# SCH_Apple_II_Game_port_2024-02-08.net
KiCad netlist of a schematic drawn in EasyEDA
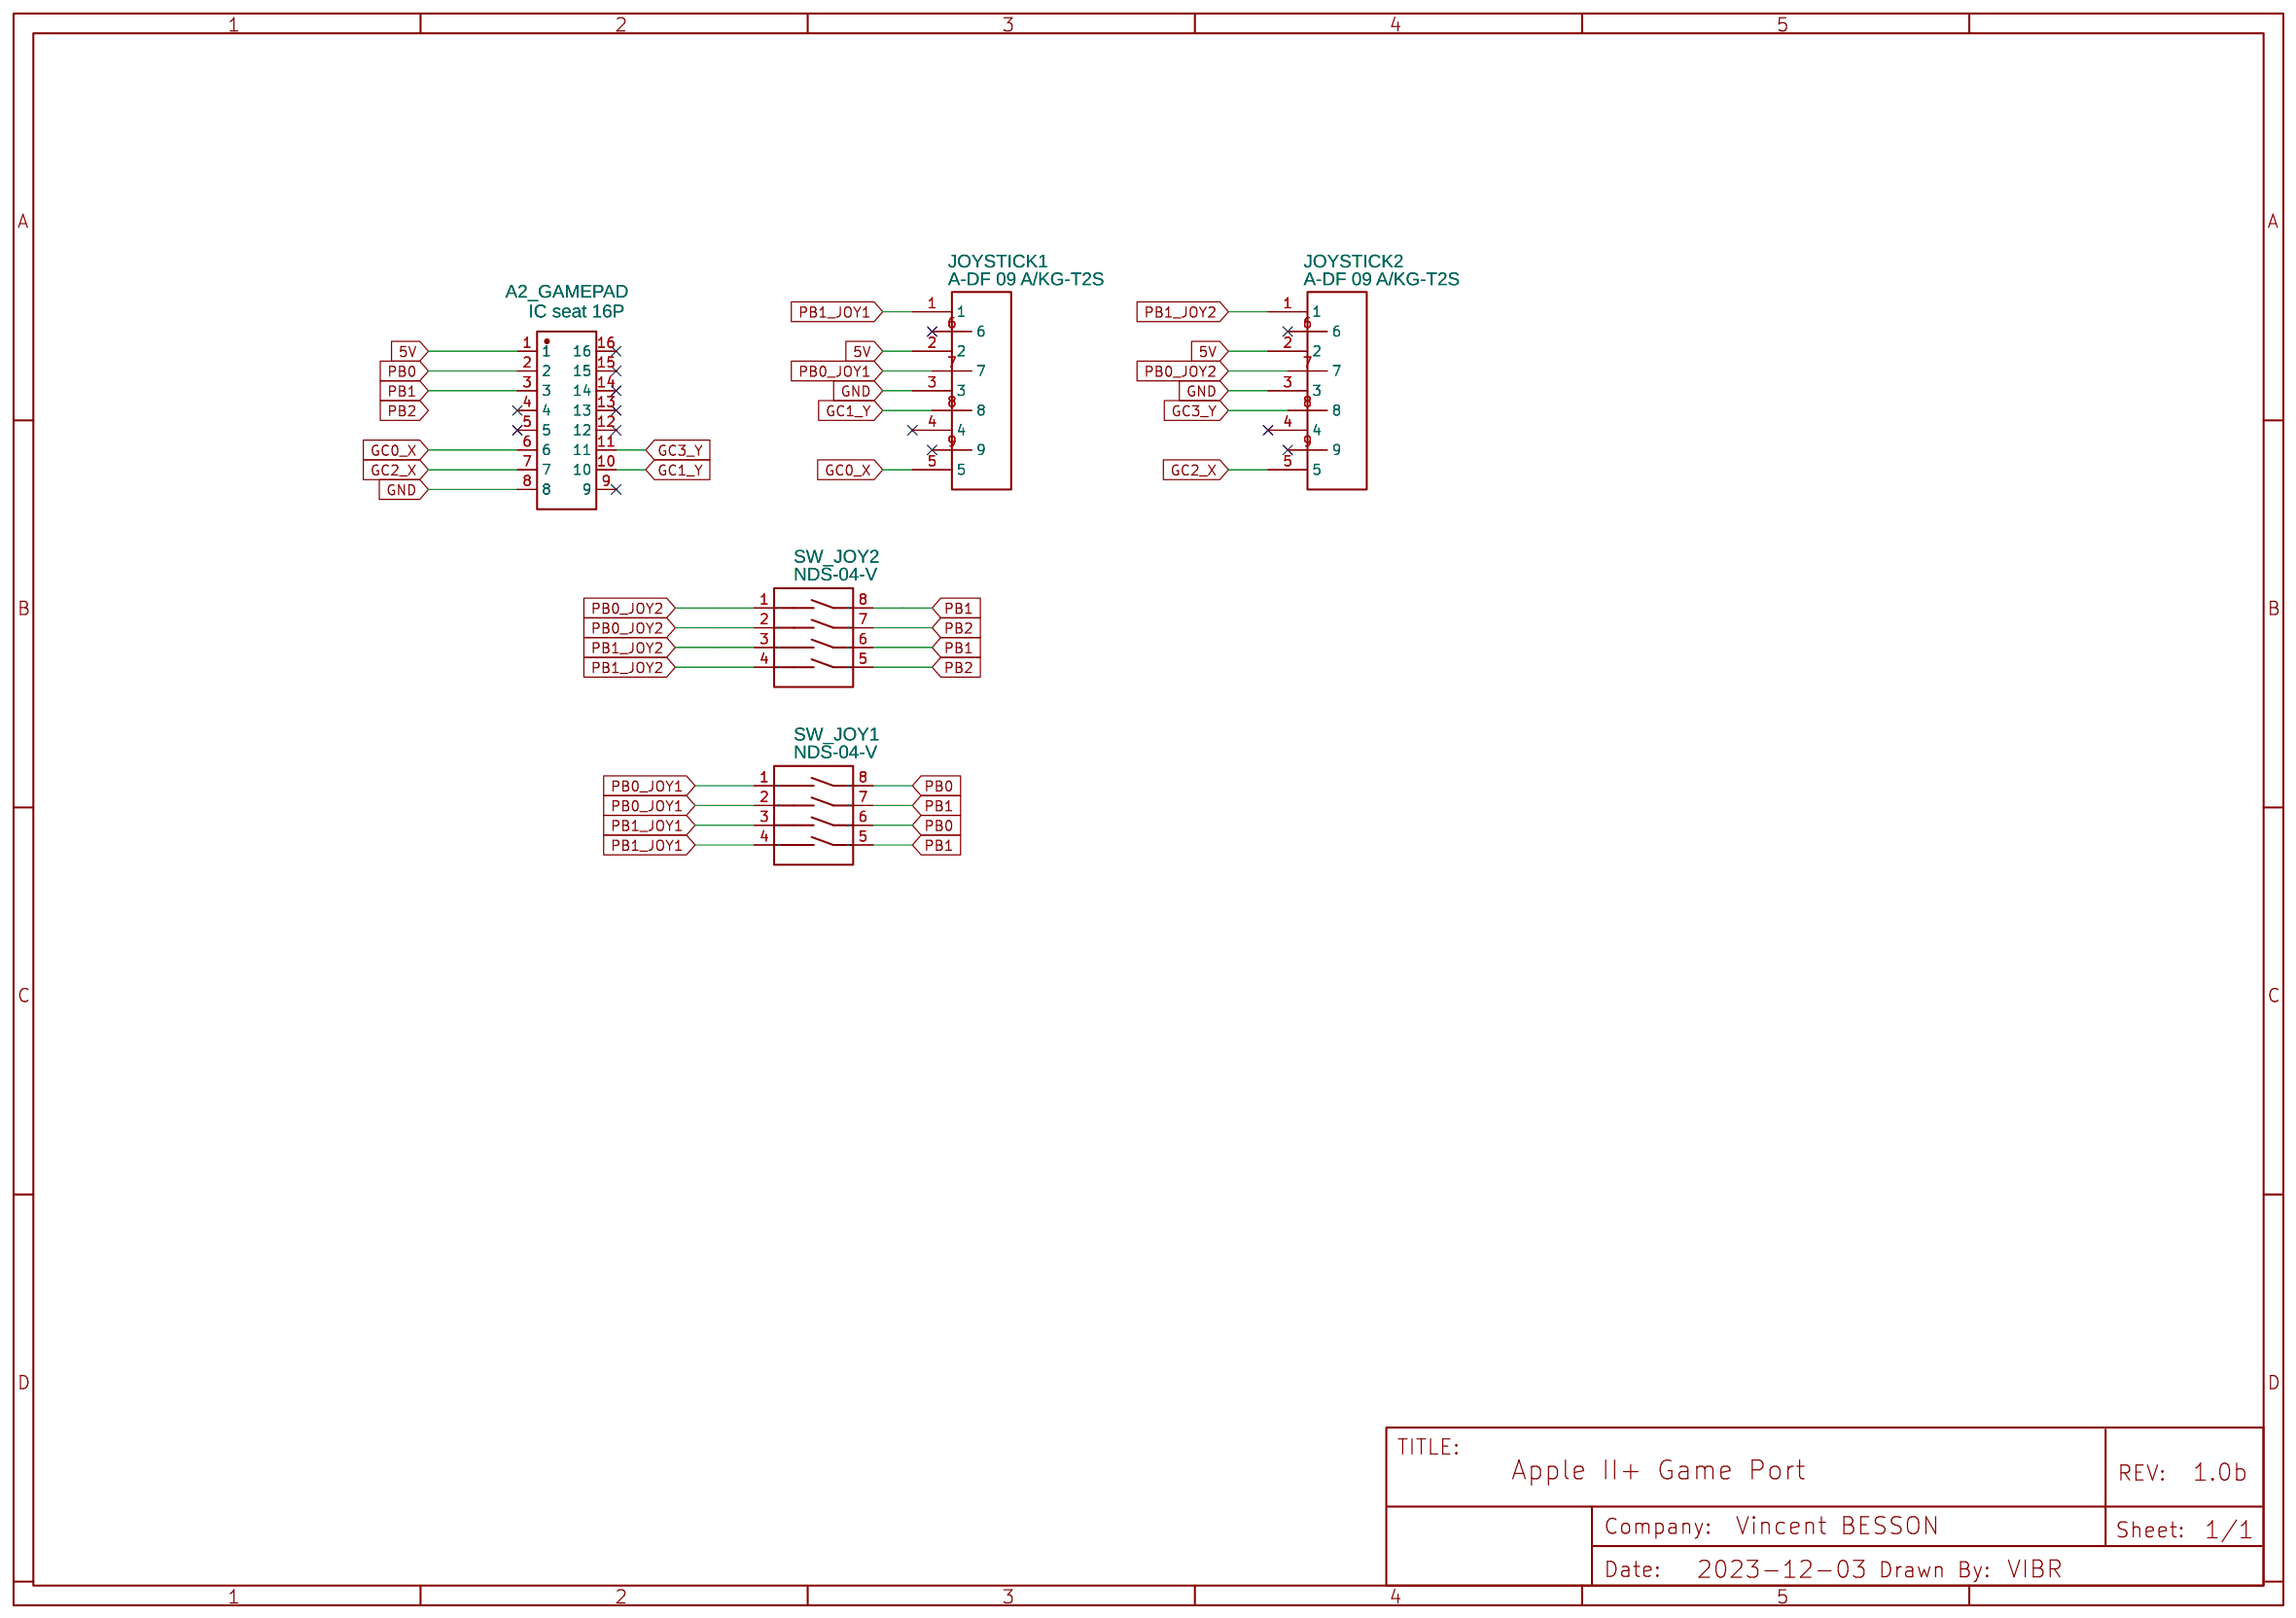
[diagram p0: schematic sheet]

(export (version "E")
  (design (tool "Eeschema 10.0.6"))
  (components
    (comp (ref "A2_GAMEPAD")
      (value "IC seat 16P")
      (fields (field (name "Manufacturer Part") "IC-16P窄") (field (name "Manufacturer") "BOOMELE(博穆精密)"))
      (libsource (lib "") (part "IC seat 16P"))
    )
    (comp (ref "JOYSTICK1") (value "A-DF 09 A/KG-T2S") (libsource (lib "") (part "A-DF 09 A/KG-T2S")))
    (comp (ref "JOYSTICK2") (value "A-DF 09 A/KG-T2S") (libsource (lib "") (part "A-DF 09 A/KG-T2S")))
    (comp (ref "SW_JOY1")
      (value "NDS-04-V")
      (fields (field (name "Manufacturer") "DIP"))
      (libsource (lib "") (part "NDS-04-V"))
    )
    (comp (ref "SW_JOY2")
      (value "NDS-04-V")
      (fields (field (name "Manufacturer") "DIP"))
      (libsource (lib "") (part "NDS-04-V"))
    )
  )
  (nets
    (net (code "1") (name "5V") (class "Default")
      (node (ref "A2_GAMEPAD") (pin "1") (pinfunction "1_1") (pintype "unspecified"))
      (node (ref "JOYSTICK1") (pin "2") (pinfunction "2_2") (pintype "unspecified"))
      (node (ref "JOYSTICK2") (pin "2") (pinfunction "2_2") (pintype "unspecified"))
    )
    (net (code "2") (name "GC0_X") (class "Default")
      (node (ref "A2_GAMEPAD") (pin "6") (pinfunction "6_6") (pintype "unspecified"))
      (node (ref "JOYSTICK1") (pin "5") (pinfunction "5_5") (pintype "unspecified"))
    )
    (net (code "3") (name "GC1_Y") (class "Default")
      (node (ref "A2_GAMEPAD") (pin "10") (pinfunction "10_10") (pintype "unspecified"))
      (node (ref "JOYSTICK1") (pin "8") (pinfunction "8_8") (pintype "unspecified"))
    )
    (net (code "4") (name "GC2_X") (class "Default")
      (node (ref "A2_GAMEPAD") (pin "7") (pinfunction "7_7") (pintype "unspecified"))
      (node (ref "JOYSTICK2") (pin "5") (pinfunction "5_5") (pintype "unspecified"))
    )
    (net (code "5") (name "GC3_Y") (class "Default")
      (node (ref "A2_GAMEPAD") (pin "11") (pinfunction "11_11") (pintype "unspecified"))
      (node (ref "JOYSTICK2") (pin "8") (pinfunction "8_8") (pintype "unspecified"))
    )
    (net (code "6") (name "GND") (class "Default")
      (node (ref "A2_GAMEPAD") (pin "8") (pinfunction "8_8") (pintype "unspecified"))
      (node (ref "JOYSTICK1") (pin "3") (pinfunction "3_3") (pintype "unspecified"))
      (node (ref "JOYSTICK2") (pin "3") (pinfunction "3_3") (pintype "unspecified"))
    )
    (net (code "7") (name "PB0") (class "Default")
      (node (ref "A2_GAMEPAD") (pin "2") (pinfunction "2_2") (pintype "unspecified"))
      (node (ref "SW_JOY1") (pin "6") (pinfunction "6_6") (pintype "unspecified"))
      (node (ref "SW_JOY1") (pin "8") (pinfunction "8_8") (pintype "unspecified"))
    )
    (net (code "8") (name "PB0_JOY1") (class "Default")
      (node (ref "JOYSTICK1") (pin "7") (pinfunction "7_7") (pintype "unspecified"))
      (node (ref "SW_JOY1") (pin "1") (pinfunction "1_1") (pintype "unspecified"))
      (node (ref "SW_JOY1") (pin "2") (pinfunction "2_2") (pintype "unspecified"))
    )
    (net (code "9") (name "PB0_JOY2") (class "Default")
      (node (ref "JOYSTICK2") (pin "7") (pinfunction "7_7") (pintype "unspecified"))
      (node (ref "SW_JOY2") (pin "1") (pinfunction "1_1") (pintype "unspecified"))
      (node (ref "SW_JOY2") (pin "2") (pinfunction "2_2") (pintype "unspecified"))
    )
    (net (code "10") (name "PB1") (class "Default")
      (node (ref "A2_GAMEPAD") (pin "3") (pinfunction "3_3") (pintype "unspecified"))
      (node (ref "SW_JOY1") (pin "5") (pinfunction "5_5") (pintype "unspecified"))
      (node (ref "SW_JOY1") (pin "7") (pinfunction "7_7") (pintype "unspecified"))
      (node (ref "SW_JOY2") (pin "6") (pinfunction "6_6") (pintype "unspecified"))
      (node (ref "SW_JOY2") (pin "8") (pinfunction "8_8") (pintype "unspecified"))
    )
    (net (code "11") (name "PB1_JOY1") (class "Default")
      (node (ref "JOYSTICK1") (pin "1") (pinfunction "1_1") (pintype "unspecified"))
      (node (ref "SW_JOY1") (pin "3") (pinfunction "3_3") (pintype "unspecified"))
      (node (ref "SW_JOY1") (pin "4") (pinfunction "4_4") (pintype "unspecified"))
    )
    (net (code "12") (name "PB1_JOY2") (class "Default")
      (node (ref "JOYSTICK2") (pin "1") (pinfunction "1_1") (pintype "unspecified"))
      (node (ref "SW_JOY2") (pin "3") (pinfunction "3_3") (pintype "unspecified"))
      (node (ref "SW_JOY2") (pin "4") (pinfunction "4_4") (pintype "unspecified"))
    )
    (net (code "13") (name "PB2") (class "Default")
      (node (ref "SW_JOY2") (pin "5") (pinfunction "5_5") (pintype "unspecified"))
      (node (ref "SW_JOY2") (pin "7") (pinfunction "7_7") (pintype "unspecified"))
    )
    (net (code "14") (name "unconnected-(A2_GAMEPAD-Pad4)") (class "Default")
      (node (ref "A2_GAMEPAD") (pin "4") (pinfunction "4_4") (pintype "unspecified+no_connect"))
    )
    (net (code "15") (name "unconnected-(A2_GAMEPAD-Pad5)") (class "Default")
      (node (ref "A2_GAMEPAD") (pin "5") (pinfunction "5_5") (pintype "unspecified+no_connect"))
    )
    (net (code "16") (name "unconnected-(A2_GAMEPAD-Pad9)") (class "Default")
      (node (ref "A2_GAMEPAD") (pin "9") (pinfunction "9_9") (pintype "unspecified+no_connect"))
    )
    (net (code "17") (name "unconnected-(A2_GAMEPAD-Pad12)") (class "Default")
      (node (ref "A2_GAMEPAD") (pin "12") (pinfunction "12_12") (pintype "unspecified+no_connect"))
    )
    (net (code "18") (name "unconnected-(A2_GAMEPAD-Pad13)") (class "Default")
      (node (ref "A2_GAMEPAD") (pin "13") (pinfunction "13_13") (pintype "unspecified+no_connect"))
    )
    (net (code "19") (name "unconnected-(A2_GAMEPAD-Pad14)") (class "Default")
      (node (ref "A2_GAMEPAD") (pin "14") (pinfunction "14_14") (pintype "unspecified+no_connect"))
    )
    (net (code "20") (name "unconnected-(A2_GAMEPAD-Pad15)") (class "Default")
      (node (ref "A2_GAMEPAD") (pin "15") (pinfunction "15_15") (pintype "unspecified+no_connect"))
    )
    (net (code "21") (name "unconnected-(A2_GAMEPAD-Pad16)") (class "Default")
      (node (ref "A2_GAMEPAD") (pin "16") (pinfunction "16_16") (pintype "unspecified+no_connect"))
    )
    (net (code "22") (name "unconnected-(JOYSTICK1-Pad4)") (class "Default")
      (node (ref "JOYSTICK1") (pin "4") (pinfunction "4_4") (pintype "unspecified+no_connect"))
    )
    (net (code "23") (name "unconnected-(JOYSTICK1-Pad6)") (class "Default")
      (node (ref "JOYSTICK1") (pin "6") (pinfunction "6_6") (pintype "unspecified+no_connect"))
    )
    (net (code "24") (name "unconnected-(JOYSTICK1-Pad9)") (class "Default")
      (node (ref "JOYSTICK1") (pin "9") (pinfunction "9_9") (pintype "unspecified+no_connect"))
    )
    (net (code "25") (name "unconnected-(JOYSTICK2-Pad4)") (class "Default")
      (node (ref "JOYSTICK2") (pin "4") (pinfunction "4_4") (pintype "unspecified+no_connect"))
    )
    (net (code "26") (name "unconnected-(JOYSTICK2-Pad6)") (class "Default")
      (node (ref "JOYSTICK2") (pin "6") (pinfunction "6_6") (pintype "unspecified+no_connect"))
    )
    (net (code "27") (name "unconnected-(JOYSTICK2-Pad9)") (class "Default")
      (node (ref "JOYSTICK2") (pin "9") (pinfunction "9_9") (pintype "unspecified+no_connect"))
    )
  )
)
